# transistorAndResistorWithSupplyAndTestPo.net
KiCad netlist of a schematic drawn in EAGLE
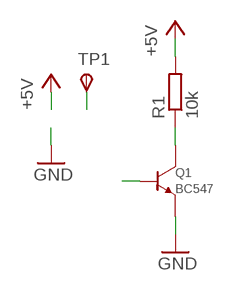
[diagram p0: schematic, sheet 1]

(export (version "E")
  (design (tool "Eeschema 10.0.6"))
  (components
    (comp (ref "Q1")
      (value "BC547")
      (footprint "eagle-import:SOT23")
      (libsource (lib "eagle-import") (part "TRANSISTOR-NPN-GENERIC-SOT23-BECDEFAULT"))
    )
    (comp (ref "R1")
      (value "10k")
      (footprint "eagle-import:R0603")
      (libsource (lib "eagle-import") (part "R-EU_R0603"))
    )
    (comp (ref "TP1")
      (value "TPSTP15R")
      (footprint "eagle-import:TP15R")
      (libsource (lib "eagle-import") (part "TPSTP15R"))
    )
  )
  (nets
    (net (code "1") (name "+5V") (class "Default")
      (node (ref "R1") (pin "2") (pinfunction "2_2") (pintype "passive"))
    )
    (net (code "2") (name "/COLLECTOR") (class "Default")
      (node (ref "Q1") (pin "P$3") (pinfunction "COLLECTOR_P$3") (pintype "bidirectional"))
      (node (ref "R1") (pin "1") (pinfunction "1_1") (pintype "passive"))
      (node (ref "TP1") (pin "TP") (pinfunction "PP_TP") (pintype "input"))
    )
    (net (code "3") (name "GND") (class "Default")
      (node (ref "Q1") (pin "P$2") (pinfunction "EMITTER_P$2") (pintype "bidirectional"))
    )
    (net (code "4") (name "unconnected-(Q1-BASE-PadP$1)") (class "Default")
      (node (ref "Q1") (pin "P$1") (pinfunction "BASE_P$1") (pintype "bidirectional"))
    )
  )
)
